# Mini_Radio_Station.net
KiCad netlist of a schematic drawn in EAGLE
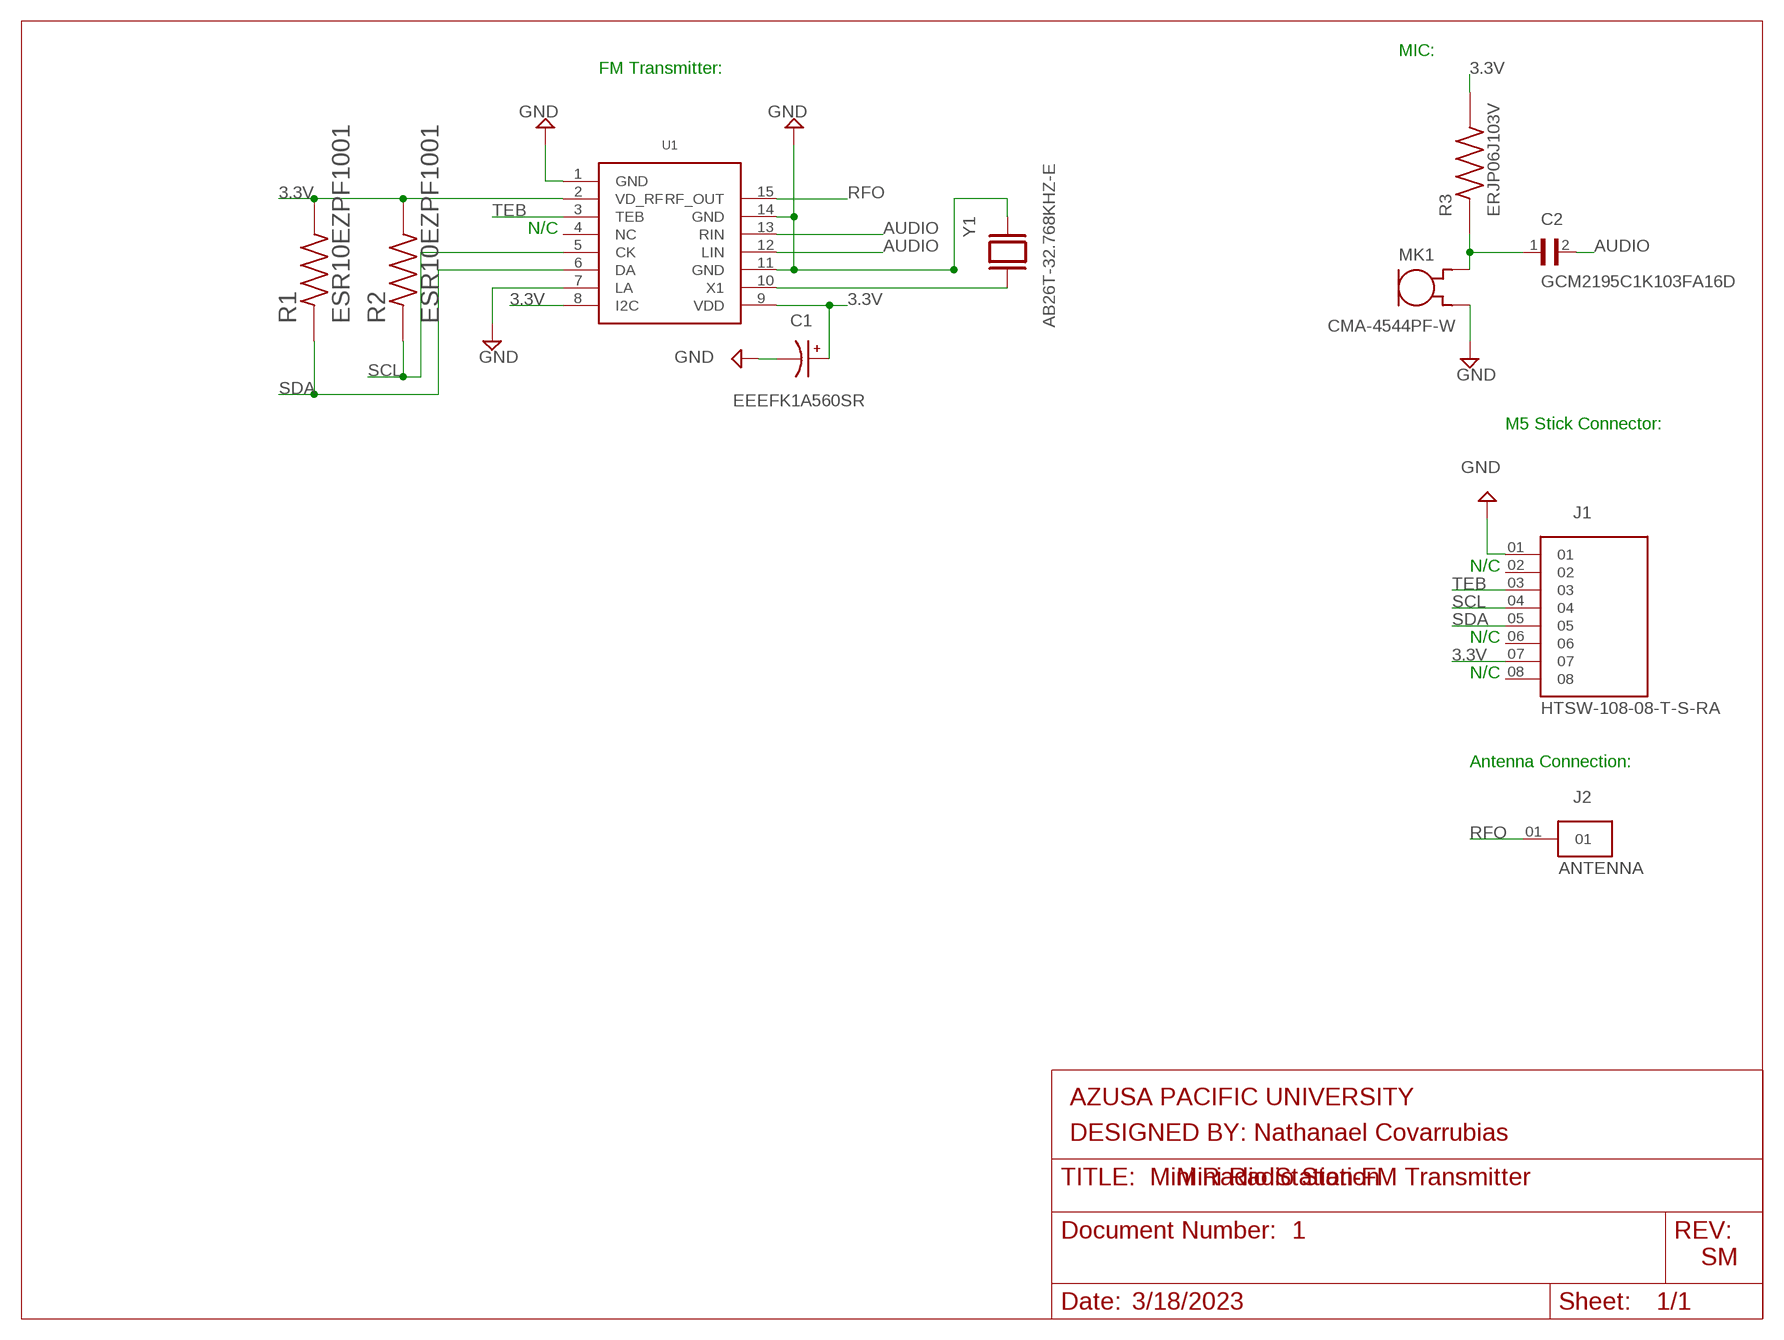
[diagram p0: schematic, sheet 1]

(export (version "E")
  (design (tool "Eeschema 10.0.6"))
  (components
    (comp (ref "C1")
      (value "EEEFK1A560SR")
      (footprint "eagle-import:CAP_EEEFK1A560SR")
      (fields (field (name "MF") "Panasonic Electronic Components") (field (name "MP") "EEE-FK1A560SR"))
      (libsource (lib "eagle-import") (part "EEEFK1A560SR"))
    )
    (comp (ref "C2")
      (value "GCM2195C1K103FA16D")
      (footprint "eagle-import:CAPC2012X95N")
      (fields (field (name "MF") "Murata"))
      (libsource (lib "eagle-import") (part "GCM2195C1K103FA16D"))
    )
    (comp (ref "J1")
      (value "HTSW-108-08-T-S-RA")
      (footprint "eagle-import:SAMTEC_HTSW-108-08-T-S-RA")
      (fields (field (name "MANUFACTURER") "Samtec"))
      (libsource (lib "eagle-import") (part "HTSW-108-08-T-S-RA"))
    )
    (comp (ref "J2")
      (value "ANTENNA")
      (footprint "eagle-import:ANTENNA")
      (libsource (lib "eagle-import") (part "ANTENNA"))
    )
    (comp (ref "MK1")
      (value "CMA-4544PF-W")
      (footprint "eagle-import:MIC_CMA-4544PF-W")
      (fields (field (name "MF") "CUI Devices"))
      (libsource (lib "eagle-import") (part "CMA-4544PF-W"))
    )
    (comp (ref "R1")
      (value "ESR10EZPF1001")
      (footprint "eagle-import:RESC2012X65N")
      (fields (field (name "MF") "Rohm"))
      (libsource (lib "eagle-import") (part "ESR10EZPF1001"))
    )
    (comp (ref "R2")
      (value "ESR10EZPF1001")
      (footprint "eagle-import:RESC2012X65N")
      (fields (field (name "MF") "Rohm"))
      (libsource (lib "eagle-import") (part "ESR10EZPF1001"))
    )
    (comp (ref "R3")
      (value "ERJP06J103V")
      (footprint "eagle-import:RES_ERJP06J103V")
      (fields (field (name "MF") "Panasonic Electronic") (field (name "MP") "ERJ-P06J103V"))
      (libsource (lib "eagle-import") (part "ERJP06J103V"))
    )
    (comp (ref "U1")
      (value "NS73M")
      (footprint "eagle-import:NS73M")
      (libsource (lib "eagle-import") (part "NS73M"))
    )
    (comp (ref "Y1")
      (value "AB26T-32.768KHZ-E")
      (footprint "eagle-import:XTAL_AB26T-32.768KHZ-E")
      (fields (field (name "MF") "Abracon LLC"))
      (libsource (lib "eagle-import") (part "AB26T-32.768KHZ-E"))
    )
  )
  (nets
    (net (code "1") (name "/3.3V") (class "Default")
      (node (ref "C1") (pin "1") (pinfunction "1_1") (pintype "passive"))
      (node (ref "J1") (pin "07") (pinfunction "07_07") (pintype "passive"))
      (node (ref "R1") (pin "2") (pinfunction "2_2") (pintype "passive"))
      (node (ref "R2") (pin "2") (pinfunction "2_2") (pintype "passive"))
      (node (ref "R3") (pin "2") (pinfunction "2_2") (pintype "passive"))
      (node (ref "U1") (pin "2") (pinfunction "VD_RF_2") (pintype "bidirectional"))
      (node (ref "U1") (pin "8") (pinfunction "I2C_8") (pintype "bidirectional"))
      (node (ref "U1") (pin "9") (pinfunction "VDD_9") (pintype "bidirectional"))
    )
    (net (code "2") (name "/AUDIO") (class "Default")
      (node (ref "C2") (pin "2") (pinfunction "2_2") (pintype "passive"))
      (node (ref "U1") (pin "12") (pinfunction "LIN_12") (pintype "bidirectional"))
      (node (ref "U1") (pin "13") (pinfunction "RIN_13") (pintype "bidirectional"))
    )
    (net (code "3") (name "/RFO") (class "Default")
      (node (ref "J2") (pin "01") (pinfunction "01_01") (pintype "passive"))
      (node (ref "U1") (pin "15") (pinfunction "RF_OUT_15") (pintype "bidirectional"))
    )
    (net (code "4") (name "/SCL") (class "Default")
      (node (ref "J1") (pin "04") (pinfunction "04_04") (pintype "passive"))
      (node (ref "R2") (pin "1") (pinfunction "1_1") (pintype "passive"))
      (node (ref "U1") (pin "5") (pinfunction "CK_5") (pintype "bidirectional"))
    )
    (net (code "5") (name "/SDA") (class "Default")
      (node (ref "J1") (pin "05") (pinfunction "05_05") (pintype "passive"))
      (node (ref "R1") (pin "1") (pinfunction "1_1") (pintype "passive"))
      (node (ref "U1") (pin "6") (pinfunction "DA_6") (pintype "bidirectional"))
    )
    (net (code "6") (name "/TEB") (class "Default")
      (node (ref "J1") (pin "03") (pinfunction "03_03") (pintype "passive"))
      (node (ref "U1") (pin "3") (pinfunction "TEB_3") (pintype "bidirectional"))
    )
    (net (code "7") (name "GND") (class "Default")
      (node (ref "C1") (pin "2") (pinfunction "2_2") (pintype "passive"))
      (node (ref "J1") (pin "01") (pinfunction "01_01") (pintype "passive"))
      (node (ref "MK1") (pin "2") (pinfunction "GND_2") (pintype "power_in"))
      (node (ref "U1") (pin "1") (pinfunction "GND_1") (pintype "bidirectional"))
      (node (ref "U1") (pin "11") (pinfunction "GND_11") (pintype "bidirectional"))
      (node (ref "U1") (pin "14") (pinfunction "GND_14") (pintype "bidirectional"))
      (node (ref "U1") (pin "7") (pinfunction "LA_7") (pintype "bidirectional"))
      (node (ref "Y1") (pin "1") (pinfunction "1_1") (pintype "passive"))
    )
    (net (code "8") (name "Net-(MK1-OUT)") (class "Default")
      (node (ref "C2") (pin "1") (pinfunction "1_1") (pintype "passive"))
      (node (ref "MK1") (pin "1") (pinfunction "OUT_1") (pintype "output"))
      (node (ref "R3") (pin "1") (pinfunction "1_1") (pintype "passive"))
    )
    (net (code "9") (name "Net-(U1-X1)") (class "Default")
      (node (ref "U1") (pin "10") (pinfunction "X1_10") (pintype "bidirectional"))
      (node (ref "Y1") (pin "2") (pinfunction "2_2") (pintype "passive"))
    )
    (net (code "10") (name "unconnected-(J1-Pad02)") (class "Default")
      (node (ref "J1") (pin "02") (pinfunction "02_02") (pintype "passive"))
    )
    (net (code "11") (name "unconnected-(J1-Pad06)") (class "Default")
      (node (ref "J1") (pin "06") (pinfunction "06_06") (pintype "passive"))
    )
    (net (code "12") (name "unconnected-(J1-Pad08)") (class "Default")
      (node (ref "J1") (pin "08") (pinfunction "08_08") (pintype "passive"))
    )
    (net (code "13") (name "unconnected-(U1-NC-Pad4)") (class "Default")
      (node (ref "U1") (pin "4") (pinfunction "NC_4") (pintype "bidirectional"))
    )
  )
)
